# vhf-radio.net
KiCad netlist of a schematic drawn in EAGLE
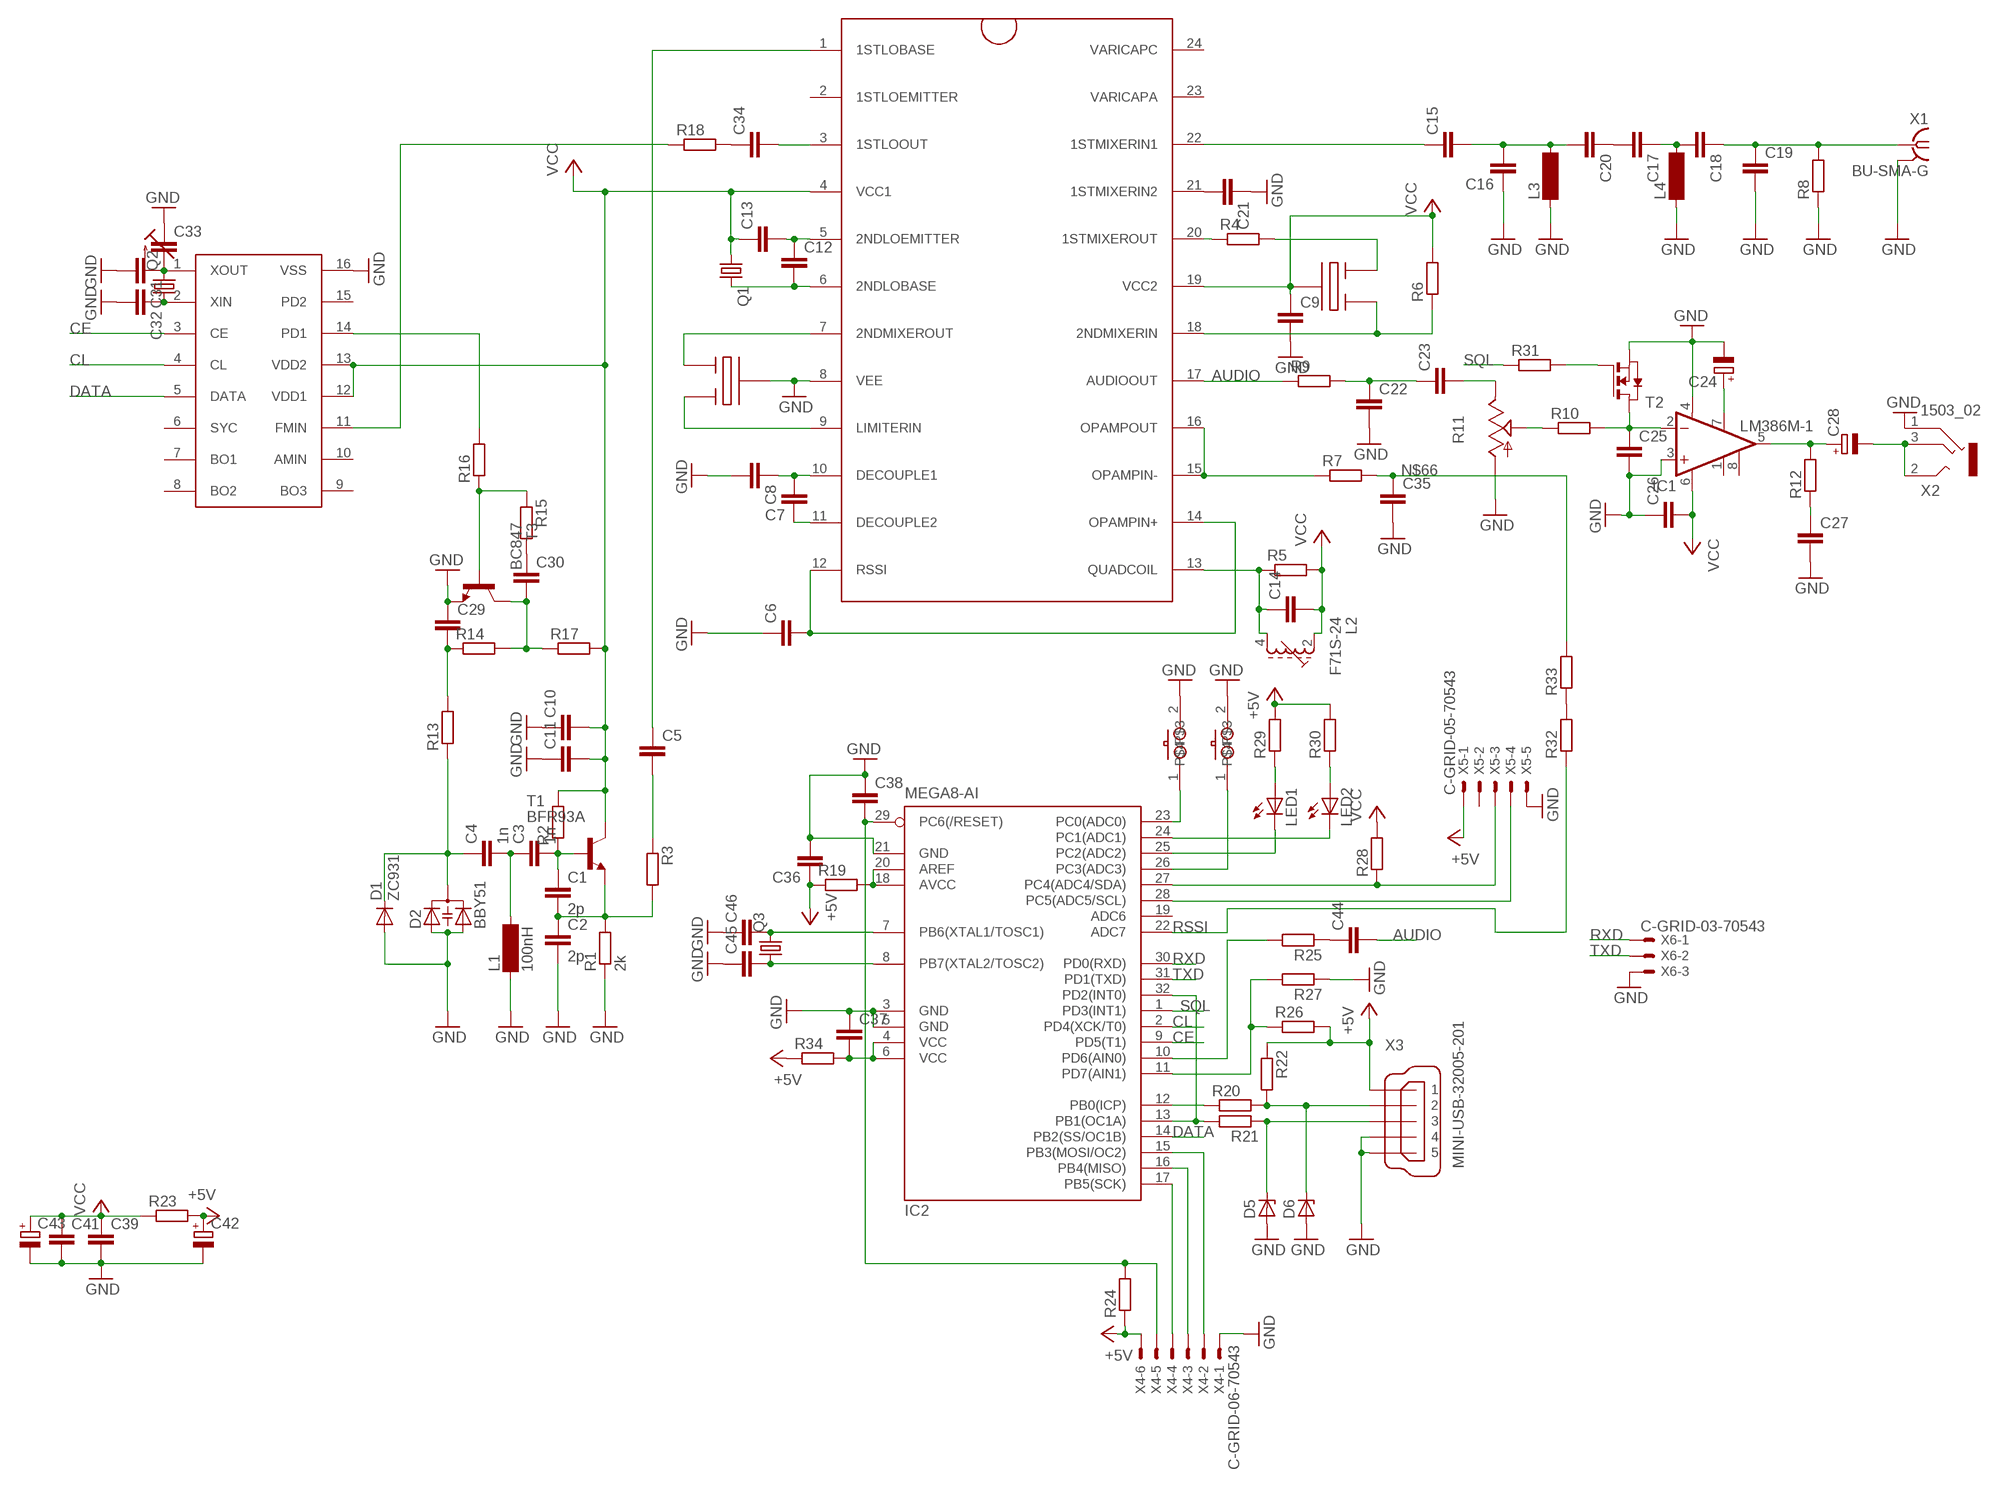
[diagram p0: schematic, sheet 1]

(export (version "E")
  (design (tool "Eeschema 10.0.6"))
  (components
    (comp (ref "C1")
      (value "2p")
      (footprint "eagle-import:C0805")
      (libsource (lib "eagle-import") (part "resistor_C-EUC0805"))
    )
    (comp (ref "C2")
      (value "2p")
      (footprint "eagle-import:C0805")
      (libsource (lib "eagle-import") (part "resistor_C-EUC0805"))
    )
    (comp (ref "C3")
      (value "1n")
      (footprint "eagle-import:C0805")
      (libsource (lib "eagle-import") (part "resistor_C-EUC0805"))
    )
    (comp (ref "C4")
      (value "1n")
      (footprint "eagle-import:C0805")
      (libsource (lib "eagle-import") (part "resistor_C-EUC0805"))
    )
    (comp (ref "C5")
      (value "C-EUC0805")
      (footprint "eagle-import:C0805")
      (libsource (lib "eagle-import") (part "C-EUC0805"))
    )
    (comp (ref "C6")
      (value "C-EUC0805")
      (footprint "eagle-import:C0805")
      (libsource (lib "eagle-import") (part "C-EUC0805"))
    )
    (comp (ref "C7")
      (value "C-EUC0805")
      (footprint "eagle-import:C0805")
      (libsource (lib "eagle-import") (part "C-EUC0805"))
    )
    (comp (ref "C8")
      (value "C-EUC0805")
      (footprint "eagle-import:C0805")
      (libsource (lib "eagle-import") (part "C-EUC0805"))
    )
    (comp (ref "C9")
      (value "C-EUC0805")
      (footprint "eagle-import:C0805")
      (libsource (lib "eagle-import") (part "C-EUC0805"))
    )
    (comp (ref "C10")
      (value "C-EUC0805")
      (footprint "eagle-import:C0805")
      (libsource (lib "eagle-import") (part "C-EUC0805"))
    )
    (comp (ref "C11")
      (value "C-EUC0805")
      (footprint "eagle-import:C0805")
      (libsource (lib "eagle-import") (part "C-EUC0805"))
    )
    (comp (ref "C12")
      (value "C-EUC0805")
      (footprint "eagle-import:C0805")
      (libsource (lib "eagle-import") (part "resistor_C-EUC0805"))
    )
    (comp (ref "C13")
      (value "C-EUC0805")
      (footprint "eagle-import:C0805")
      (libsource (lib "eagle-import") (part "resistor_C-EUC0805"))
    )
    (comp (ref "C14")
      (value "C-EUC0805")
      (footprint "eagle-import:C0805")
      (libsource (lib "eagle-import") (part "C-EUC0805"))
    )
    (comp (ref "C15")
      (value "C-EUC0805")
      (footprint "eagle-import:C0805")
      (libsource (lib "eagle-import") (part "resistor_C-EUC0805"))
    )
    (comp (ref "C16")
      (value "C-EUC0805")
      (footprint "eagle-import:C0805")
      (libsource (lib "eagle-import") (part "resistor_C-EUC0805"))
    )
    (comp (ref "C17")
      (value "C-EUC0805")
      (footprint "eagle-import:C0805")
      (libsource (lib "eagle-import") (part "resistor_C-EUC0805"))
    )
    (comp (ref "C18")
      (value "C-EUC0805")
      (footprint "eagle-import:C0805")
      (libsource (lib "eagle-import") (part "resistor_C-EUC0805"))
    )
    (comp (ref "C19")
      (value "C-EUC0805")
      (footprint "eagle-import:C0805")
      (libsource (lib "eagle-import") (part "resistor_C-EUC0805"))
    )
    (comp (ref "C20")
      (value "C-EUC0805")
      (footprint "eagle-import:C0805")
      (libsource (lib "eagle-import") (part "resistor_C-EUC0805"))
    )
    (comp (ref "C21")
      (value "C-EUC0805")
      (footprint "eagle-import:C0805")
      (libsource (lib "eagle-import") (part "resistor_C-EUC0805"))
    )
    (comp (ref "C22")
      (value "C-EUC0805")
      (footprint "eagle-import:C0805")
      (libsource (lib "eagle-import") (part "resistor_C-EUC0805"))
    )
    (comp (ref "C23")
      (value "C-EUC0805")
      (footprint "eagle-import:C0805")
      (libsource (lib "eagle-import") (part "resistor_C-EUC0805"))
    )
    (comp (ref "C24")
      (value "CPOL-EU153CLV-0505")
      (footprint "eagle-import:153CLV-0505")
      (libsource (lib "eagle-import") (part "CPOL-EU153CLV-0505"))
    )
    (comp (ref "C25")
      (value "C-EUC0805")
      (footprint "eagle-import:C0805")
      (libsource (lib "eagle-import") (part "C-EUC0805"))
    )
    (comp (ref "C26")
      (value "C-EUC0805")
      (footprint "eagle-import:C0805")
      (libsource (lib "eagle-import") (part "C-EUC0805"))
    )
    (comp (ref "C27")
      (value "C-EUC0805")
      (footprint "eagle-import:C0805")
      (libsource (lib "eagle-import") (part "C-EUC0805"))
    )
    (comp (ref "C28")
      (value "CPOL-EU153CLV-0605")
      (footprint "eagle-import:153CLV-0605")
      (libsource (lib "eagle-import") (part "resistor_CPOL-EU153CLV-0605"))
    )
    (comp (ref "C29")
      (value "C-EUC0805")
      (footprint "eagle-import:C0805")
      (libsource (lib "eagle-import") (part "C-EUC0805"))
    )
    (comp (ref "C30")
      (value "C-EUC0805")
      (footprint "eagle-import:C0805")
      (libsource (lib "eagle-import") (part "C-EUC0805"))
    )
    (comp (ref "C31")
      (value "C-EUC0805")
      (footprint "eagle-import:C0805")
      (libsource (lib "eagle-import") (part "C-EUC0805"))
    )
    (comp (ref "C32")
      (value "C-EUC0805")
      (footprint "eagle-import:C0805")
      (libsource (lib "eagle-import") (part "C-EUC0805"))
    )
    (comp (ref "C33")
      (value "C-TRIMM3018_12")
      (footprint "eagle-import:CTRIM3018_12")
      (libsource (lib "eagle-import") (part "C-TRIMM3018_12"))
    )
    (comp (ref "C34")
      (value "C-EUC0805")
      (footprint "eagle-import:C0805")
      (libsource (lib "eagle-import") (part "C-EUC0805"))
    )
    (comp (ref "C35")
      (value "C-EUC0805")
      (footprint "eagle-import:C0805")
      (libsource (lib "eagle-import") (part "C-EUC0805"))
    )
    (comp (ref "C36")
      (value "C-EUC0805")
      (footprint "eagle-import:C0805")
      (libsource (lib "eagle-import") (part "C-EUC0805"))
    )
    (comp (ref "C37")
      (value "C-EUC0805")
      (footprint "eagle-import:C0805")
      (libsource (lib "eagle-import") (part "C-EUC0805"))
    )
    (comp (ref "C38")
      (value "C-EU075-032X103")
      (footprint "eagle-import:C075-032X103")
      (libsource (lib "eagle-import") (part "C-EU075-032X103"))
    )
    (comp (ref "C39")
      (value "C-EUC0805")
      (footprint "eagle-import:C0805")
      (libsource (lib "eagle-import") (part "C-EUC0805"))
    )
    (comp (ref "C41")
      (value "C-EUC0805")
      (footprint "eagle-import:C0805")
      (libsource (lib "eagle-import") (part "C-EUC0805"))
    )
    (comp (ref "C42")
      (value "CPOL-EU175TMP-0808")
      (footprint "eagle-import:175TMP-0808")
      (libsource (lib "eagle-import") (part "CPOL-EU175TMP-0808"))
    )
    (comp (ref "C43")
      (value "CPOL-EU175TMP-0808")
      (footprint "eagle-import:175TMP-0808")
      (libsource (lib "eagle-import") (part "CPOL-EU175TMP-0808"))
    )
    (comp (ref "C44")
      (value "C-EUC0805")
      (footprint "eagle-import:C0805")
      (libsource (lib "eagle-import") (part "C-EUC0805"))
    )
    (comp (ref "C45")
      (value "C-EUC0805")
      (footprint "eagle-import:C0805")
      (libsource (lib "eagle-import") (part "C-EUC0805"))
    )
    (comp (ref "C46")
      (value "C-EUC0805")
      (footprint "eagle-import:C0805")
      (libsource (lib "eagle-import") (part "C-EUC0805"))
    )
    (comp (ref "D1")
      (value "ZC931")
      (footprint "eagle-import:MINIMELF")
      (libsource (lib "eagle-import") (part "DIODE-MINIMELF"))
    )
    (comp (ref "D2")
      (value "BBY51")
      (footprint "eagle-import:SOT23")
      (libsource (lib "eagle-import") (part "BBY51"))
    )
    (comp (ref "D5")
      (value "ZENER-DIODESOD80C")
      (footprint "eagle-import:SOD80C")
      (libsource (lib "eagle-import") (part "ZENER-DIODESOD80C"))
    )
    (comp (ref "D6")
      (value "ZENER-DIODESOD80C")
      (footprint "eagle-import:SOD80C")
      (libsource (lib "eagle-import") (part "ZENER-DIODESOD80C"))
    )
    (comp (ref "IC1")
      (value "LM386M-1")
      (footprint "eagle-import:SO08")
      (libsource (lib "eagle-import") (part "LM386?-M1"))
    )
    (comp (ref "IC2")
      (value "MEGA8-AI")
      (footprint "eagle-import:TQFP32-08")
      (libsource (lib "eagle-import") (part "MEGA8-AI"))
    )
    (comp (ref "L1")
      (value "100nH")
      (footprint "eagle-import:SM-1206")
      (libsource (lib "eagle-import") (part "SM-1206"))
    )
    (comp (ref "L2")
      (value "F71S-24")
      (footprint "eagle-import:71S")
      (libsource (lib "eagle-import") (part "F71S-24"))
    )
    (comp (ref "L3")
      (value "SM-1206")
      (footprint "eagle-import:SM-1206")
      (libsource (lib "eagle-import") (part "SM-1206"))
    )
    (comp (ref "L4")
      (value "SM-1206")
      (footprint "eagle-import:SM-1206")
      (libsource (lib "eagle-import") (part "SM-1206"))
    )
    (comp (ref "LED1")
      (value "LEDCHIPLED_0805")
      (footprint "eagle-import:CHIPLED_0805")
      (libsource (lib "eagle-import") (part "LEDCHIPLED_0805"))
    )
    (comp (ref "LED2")
      (value "LEDCHIPLED_0805")
      (footprint "eagle-import:CHIPLED_0805")
      (libsource (lib "eagle-import") (part "LEDCHIPLED_0805"))
    )
    (comp (ref "Q1")
      (value "CRYSTALHC49UP")
      (footprint "eagle-import:HC49UP")
      (libsource (lib "eagle-import") (part "CRYSTALHC49UP"))
    )
    (comp (ref "Q2")
      (value "CRYSTALHC49UP")
      (footprint "eagle-import:HC49UP")
      (libsource (lib "eagle-import") (part "CRYSTALHC49UP"))
    )
    (comp (ref "Q3")
      (value "CRYSTALHC49UP")
      (footprint "eagle-import:HC49UP")
      (libsource (lib "eagle-import") (part "CRYSTALHC49UP"))
    )
    (comp (ref "R1")
      (value "2k")
      (footprint "eagle-import:R0805")
      (libsource (lib "eagle-import") (part "resistor_R-EU_R0805"))
    )
    (comp (ref "R2")
      (value "R-EU_R0805")
      (footprint "eagle-import:R0805")
      (libsource (lib "eagle-import") (part "resistor_R-EU_R0805"))
    )
    (comp (ref "R3")
      (value "R-EU_R0805")
      (footprint "eagle-import:R0805")
      (libsource (lib "eagle-import") (part "R-EU_R0805"))
    )
    (comp (ref "R4")
      (value "R-EU_R0805")
      (footprint "eagle-import:R0805")
      (libsource (lib "eagle-import") (part "R-EU_R0805"))
    )
    (comp (ref "R5")
      (value "R-EU_R0805")
      (footprint "eagle-import:R0805")
      (libsource (lib "eagle-import") (part "R-EU_R0805"))
    )
    (comp (ref "R6")
      (value "R-EU_R0805")
      (footprint "eagle-import:R0805")
      (libsource (lib "eagle-import") (part "R-EU_R0805"))
    )
    (comp (ref "R7")
      (value "R-EU_R0805")
      (footprint "eagle-import:R0805")
      (libsource (lib "eagle-import") (part "R-EU_R0805"))
    )
    (comp (ref "R8")
      (value "R-EU_R0805")
      (footprint "eagle-import:R0805")
      (libsource (lib "eagle-import") (part "resistor_R-EU_R0805"))
    )
    (comp (ref "R9")
      (value "R-EU_R0805")
      (footprint "eagle-import:R0805")
      (libsource (lib "eagle-import") (part "R-EU_R0805"))
    )
    (comp (ref "R10")
      (value "R-EU_R0805")
      (footprint "eagle-import:R0805")
      (libsource (lib "eagle-import") (part "R-EU_R0805"))
    )
    (comp (ref "R11")
      (value "TRIM_US-CIP20C-6MM")
      (footprint "eagle-import:CIP20C-6MM")
      (libsource (lib "eagle-import") (part "TRIM_US-CIP20C-6MM"))
    )
    (comp (ref "R12")
      (value "R-EU_R0805")
      (footprint "eagle-import:R0805")
      (libsource (lib "eagle-import") (part "R-EU_R0805"))
    )
    (comp (ref "R13")
      (value "R-EU_R0805")
      (footprint "eagle-import:R0805")
      (libsource (lib "eagle-import") (part "R-EU_R0805"))
    )
    (comp (ref "R14")
      (value "R-EU_R0805")
      (footprint "eagle-import:R0805")
      (libsource (lib "eagle-import") (part "R-EU_R0805"))
    )
    (comp (ref "R15")
      (value "R-EU_R0805")
      (footprint "eagle-import:R0805")
      (libsource (lib "eagle-import") (part "R-EU_R0805"))
    )
    (comp (ref "R16")
      (value "R-EU_R0805")
      (footprint "eagle-import:R0805")
      (libsource (lib "eagle-import") (part "R-EU_R0805"))
    )
    (comp (ref "R17")
      (value "R-EU_R0805")
      (footprint "eagle-import:R0805")
      (libsource (lib "eagle-import") (part "R-EU_R0805"))
    )
    (comp (ref "R18")
      (value "R-EU_R0805")
      (footprint "eagle-import:R0805")
      (libsource (lib "eagle-import") (part "R-EU_R0805"))
    )
    (comp (ref "R19")
      (value "R-EU_R0805")
      (footprint "eagle-import:R0805")
      (libsource (lib "eagle-import") (part "R-EU_R0805"))
    )
    (comp (ref "R20")
      (value "R-EU_R0805")
      (footprint "eagle-import:R0805")
      (libsource (lib "eagle-import") (part "R-EU_R0805"))
    )
    (comp (ref "R21")
      (value "R-EU_R0805")
      (footprint "eagle-import:R0805")
      (libsource (lib "eagle-import") (part "R-EU_R0805"))
    )
    (comp (ref "R22")
      (value "R-EU_R0805")
      (footprint "eagle-import:R0805")
      (libsource (lib "eagle-import") (part "R-EU_R0805"))
    )
    (comp (ref "R23")
      (value "R-EU_0207/10")
      (footprint "eagle-import:0207_10")
      (libsource (lib "eagle-import") (part "resistor_R-EU_0207/10"))
    )
    (comp (ref "R24")
      (value "R-EU_R0805")
      (footprint "eagle-import:R0805")
      (libsource (lib "eagle-import") (part "R-EU_R0805"))
    )
    (comp (ref "R25")
      (value "R-EU_R0805")
      (footprint "eagle-import:R0805")
      (libsource (lib "eagle-import") (part "R-EU_R0805"))
    )
    (comp (ref "R26")
      (value "R-EU_R0805")
      (footprint "eagle-import:R0805")
      (libsource (lib "eagle-import") (part "R-EU_R0805"))
    )
    (comp (ref "R27")
      (value "R-EU_R0805")
      (footprint "eagle-import:R0805")
      (libsource (lib "eagle-import") (part "R-EU_R0805"))
    )
    (comp (ref "R28")
      (value "R-EU_0207/10")
      (footprint "eagle-import:0207_10")
      (libsource (lib "eagle-import") (part "resistor_R-EU_0207/10"))
    )
    (comp (ref "R29")
      (value "R-EU_R0805")
      (footprint "eagle-import:R0805")
      (libsource (lib "eagle-import") (part "R-EU_R0805"))
    )
    (comp (ref "R30")
      (value "R-EU_R0805")
      (footprint "eagle-import:R0805")
      (libsource (lib "eagle-import") (part "R-EU_R0805"))
    )
    (comp (ref "R31")
      (value "R-EU_R1206")
      (footprint "eagle-import:R1206")
      (libsource (lib "eagle-import") (part "R-EU_R1206"))
    )
    (comp (ref "R32")
      (value "R-EU_0207/10")
      (footprint "eagle-import:0207_10")
      (libsource (lib "eagle-import") (part "resistor_R-EU_0207/10"))
    )
    (comp (ref "R33")
      (value "R-EU_0207/10")
      (footprint "eagle-import:0207_10")
      (libsource (lib "eagle-import") (part "resistor_R-EU_0207/10"))
    )
    (comp (ref "R34")
      (value "R-EU_0207/10")
      (footprint "eagle-import:0207_10")
      (libsource (lib "eagle-import") (part "resistor_R-EU_0207/10"))
    )
    (comp (ref "T1")
      (value "BFR93A")
      (footprint "eagle-import:SOT23-BEC")
      (libsource (lib "eagle-import") (part "-NPN-SOT23-BECBFR53"))
    )
    (comp (ref "T2")
      (value "NMOSSOT23")
      (footprint "eagle-import:SOT-23")
      (libsource (lib "eagle-import") (part "NMOSSOT23"))
    )
    (comp (ref "T3")
      (value "BC847")
      (footprint "eagle-import:SOT23")
      (libsource (lib "eagle-import") (part "BC847"))
    )
    (comp (ref "U$1")
      (value "MC13135P-SMD")
      (footprint "eagle-import:DIP-SMD")
      (libsource (lib "eagle-import") (part "MC13135P-SMD"))
    )
    (comp (ref "U$2")
      (value "QFILTER")
      (footprint "eagle-import:SIP3-SMD")
      (libsource (lib "eagle-import") (part "QFILTER"))
    )
    (comp (ref "U$3")
      (value "QFILTER")
      (footprint "eagle-import:SIP3-SMD")
      (libsource (lib "eagle-import") (part "QFILTER"))
    )
    (comp (ref "U$4")
      (value "LM7001-DIPSMD")
      (footprint "eagle-import:DIP16-SMD")
      (libsource (lib "eagle-import") (part "LM7001-DIPSMD"))
    )
    (comp (ref "U$5")
      (value "TS-1")
      (footprint "eagle-import:TS-1")
      (libsource (lib "eagle-import") (part "TS-1"))
    )
    (comp (ref "U$6")
      (value "TS-1")
      (footprint "eagle-import:TS-1")
      (libsource (lib "eagle-import") (part "TS-1"))
    )
    (comp (ref "X1")
      (value "BU-SMA-G")
      (footprint "eagle-import:BU-SMA-G")
      (libsource (lib "eagle-import") (part "BU-SMA-G"))
    )
    (comp (ref "X2")
      (value "1503_02")
      (footprint "eagle-import:1503_02")
      (libsource (lib "eagle-import") (part "1503_02"))
    )
    (comp (ref "X3")
      (value "MINI-USB-32005-201")
      (footprint "eagle-import:32005-201")
      (libsource (lib "eagle-import") (part "MINI-USB-32005-201"))
    )
    (comp (ref "X4")
      (value "C-GRID-06-70543")
      (footprint "eagle-import:70543-06")
      (libsource (lib "eagle-import") (part "C-GRID-06-70543"))
    )
    (comp (ref "X5")
      (value "C-GRID-05-70543")
      (footprint "eagle-import:70543-05")
      (libsource (lib "eagle-import") (part "C-GRID-05-70543"))
    )
    (comp (ref "X6")
      (value "C-GRID-03-70543")
      (footprint "eagle-import:70543-03")
      (libsource (lib "eagle-import") (part "C-GRID-03-70543"))
    )
  )
  (nets
    (net (code "1") (name "+5V") (class "Default")
      (node (ref "C36") (pin "1") (pinfunction "1_1") (pintype "passive"))
      (node (ref "C42") (pin "+") (pinfunction "+_+") (pintype "passive"))
      (node (ref "R19") (pin "1") (pinfunction "1_1") (pintype "passive"))
      (node (ref "R22") (pin "1") (pinfunction "1_1") (pintype "passive"))
      (node (ref "R23") (pin "2") (pinfunction "2_2") (pintype "passive"))
      (node (ref "R24") (pin "1") (pinfunction "1_1") (pintype "passive"))
      (node (ref "R26") (pin "2") (pinfunction "2_2") (pintype "passive"))
      (node (ref "R29") (pin "2") (pinfunction "2_2") (pintype "passive"))
      (node (ref "R30") (pin "2") (pinfunction "2_2") (pintype "passive"))
      (node (ref "R34") (pin "1") (pinfunction "1_1") (pintype "passive"))
      (node (ref "X3") (pin "1") (pinfunction "1_1") (pintype "passive"))
      (node (ref "X4") (pin "6") (pinfunction "S_6") (pintype "passive"))
      (node (ref "X5") (pin "1") (pinfunction "S_1") (pintype "passive"))
    )
    (net (code "2") (name "/AUDIO") (class "Default")
      (node (ref "C44") (pin "2") (pinfunction "2_2") (pintype "passive"))
      (node (ref "R9") (pin "1") (pinfunction "1_1") (pintype "passive"))
      (node (ref "U$1") (pin "17") (pinfunction "AUDIOOUT_17") (pintype "bidirectional"))
    )
    (net (code "3") (name "/CE") (class "Default")
      (node (ref "IC2") (pin "9") (pinfunction "PD5(T1)_9") (pintype "bidirectional"))
      (node (ref "U$4") (pin "3") (pinfunction "CE_3") (pintype "bidirectional"))
    )
    (net (code "4") (name "/CL") (class "Default")
      (node (ref "IC2") (pin "2") (pinfunction "PD4(XCK/T0)_2") (pintype "bidirectional"))
      (node (ref "U$4") (pin "4") (pinfunction "CL_4") (pintype "bidirectional"))
    )
    (net (code "5") (name "/DATA") (class "Default")
      (node (ref "IC2") (pin "14") (pinfunction "PB2(SS/OC1B)_14") (pintype "bidirectional"))
      (node (ref "U$4") (pin "5") (pinfunction "DATA_5") (pintype "bidirectional"))
    )
    (net (code "6") (name "/N$66") (class "Default")
      (node (ref "C35") (pin "1") (pinfunction "1_1") (pintype "passive"))
      (node (ref "R33") (pin "2") (pinfunction "2_2") (pintype "passive"))
      (node (ref "R7") (pin "2") (pinfunction "2_2") (pintype "passive"))
    )
    (net (code "7") (name "/RSSI") (class "Default")
      (node (ref "IC2") (pin "22") (pinfunction "ADC7_22") (pintype "bidirectional"))
      (node (ref "R32") (pin "1") (pinfunction "1_1") (pintype "passive"))
    )
    (net (code "8") (name "/RXD") (class "Default")
      (node (ref "IC2") (pin "30") (pinfunction "PD0(RXD)_30") (pintype "bidirectional"))
      (node (ref "X6") (pin "1") (pinfunction "S_1") (pintype "passive"))
    )
    (net (code "9") (name "/SQL") (class "Default")
      (node (ref "IC2") (pin "1") (pinfunction "PD3(INT1)_1") (pintype "bidirectional"))
      (node (ref "R31") (pin "1") (pinfunction "1_1") (pintype "passive"))
    )
    (net (code "10") (name "/TXD") (class "Default")
      (node (ref "IC2") (pin "31") (pinfunction "PD1(TXD)_31") (pintype "bidirectional"))
      (node (ref "X6") (pin "2") (pinfunction "S_2") (pintype "passive"))
    )
    (net (code "11") (name "GND") (class "Default")
      (node (ref "C10") (pin "1") (pinfunction "1_1") (pintype "passive"))
      (node (ref "C11") (pin "1") (pinfunction "1_1") (pintype "passive"))
      (node (ref "C16") (pin "1") (pinfunction "1_1") (pintype "passive"))
      (node (ref "C19") (pin "2") (pinfunction "2_2") (pintype "passive"))
      (node (ref "C2") (pin "2") (pinfunction "2_2") (pintype "passive"))
      (node (ref "C21") (pin "1") (pinfunction "1_1") (pintype "passive"))
      (node (ref "C22") (pin "2") (pinfunction "2_2") (pintype "passive"))
      (node (ref "C24") (pin "-") (pinfunction "-_-") (pintype "passive"))
      (node (ref "C25") (pin "2") (pinfunction "2_2") (pintype "passive"))
      (node (ref "C26") (pin "1") (pinfunction "1_1") (pintype "passive"))
      (node (ref "C27") (pin "2") (pinfunction "2_2") (pintype "passive"))
      (node (ref "C29") (pin "1") (pinfunction "1_1") (pintype "passive"))
      (node (ref "C31") (pin "2") (pinfunction "2_2") (pintype "passive"))
      (node (ref "C32") (pin "2") (pinfunction "2_2") (pintype "passive"))
      (node (ref "C33") (pin "+") (pinfunction "E_+") (pintype "passive"))
      (node (ref "C35") (pin "2") (pinfunction "2_2") (pintype "passive"))
      (node (ref "C36") (pin "2") (pinfunction "2_2") (pintype "passive"))
      (node (ref "C37") (pin "1") (pinfunction "1_1") (pintype "passive"))
      (node (ref "C38") (pin "1") (pinfunction "1_1") (pintype "passive"))
      (node (ref "C39") (pin "2") (pinfunction "2_2") (pintype "passive"))
      (node (ref "C41") (pin "2") (pinfunction "2_2") (pintype "passive"))
      (node (ref "C42") (pin "-") (pinfunction "-_-") (pintype "passive"))
      (node (ref "C43") (pin "-") (pinfunction "-_-") (pintype "passive"))
      (node (ref "C45") (pin "1") (pinfunction "1_1") (pintype "passive"))
      (node (ref "C46") (pin "1") (pinfunction "1_1") (pintype "passive"))
      (node (ref "C6") (pin "1") (pinfunction "1_1") (pintype "passive"))
      (node (ref "C8") (pin "2") (pinfunction "2_2") (pintype "passive"))
      (node (ref "C9") (pin "2") (pinfunction "2_2") (pintype "passive"))
      (node (ref "D1") (pin "A") (pinfunction "A_A") (pintype "passive"))
      (node (ref "D2") (pin "1") (pinfunction "A1_1") (pintype "passive"))
      (node (ref "D2") (pin "2") (pinfunction "A2_2") (pintype "passive"))
      (node (ref "D5") (pin "A") (pinfunction "A_A") (pintype "passive"))
      (node (ref "D6") (pin "A") (pinfunction "A_A") (pintype "passive"))
      (node (ref "IC1") (pin "3") (pinfunction "+IN_3") (pintype "input"))
      (node (ref "IC1") (pin "4") (pinfunction "GND_4") (pintype "power_in"))
      (node (ref "IC2") (pin "21") (pinfunction "GND_21") (pintype "power_in"))
      (node (ref "IC2") (pin "3") (pinfunction "GND_3") (pintype "power_in"))
      (node (ref "IC2") (pin "5") (pinfunction "GND_5") (pintype "power_in"))
      (node (ref "L1") (pin "1") (pinfunction "1_1") (pintype "passive"))
      (node (ref "L3") (pin "1") (pinfunction "1_1") (pintype "passive"))
      (node (ref "L4") (pin "1") (pinfunction "1_1") (pintype "passive"))
      (node (ref "R1") (pin "1") (pinfunction "1_1") (pintype "passive"))
      (node (ref "R11") (pin "A") (pinfunction "A_A") (pintype "passive"))
      (node (ref "R27") (pin "1") (pinfunction "1_1") (pintype "passive"))
      (node (ref "R8") (pin "1") (pinfunction "1_1") (pintype "passive"))
      (node (ref "T2") (pin "2") (pinfunction "S_2") (pintype "passive"))
      (node (ref "T3") (pin "2") (pinfunction "E_2") (pintype "passive"))
      (node (ref "U$1") (pin "8") (pinfunction "VEE_8") (pintype "bidirectional"))
      (node (ref "U$2") (pin "P$2") (pinfunction "2_P$2") (pintype "bidirectional"))
      (node (ref "U$4") (pin "16") (pinfunction "VSS_16") (pintype "bidirectional"))
      (node (ref "U$5") (pin "2") (pinfunction "P$4_2") (pintype "bidirectional"))
      (node (ref "U$6") (pin "2") (pinfunction "P$4_2") (pintype "bidirectional"))
      (node (ref "X1") (pin "2") (pinfunction "GND_2") (pintype "power_in"))
      (node (ref "X2") (pin "1") (pinfunction "1_1") (pintype "passive"))
      (node (ref "X3") (pin "4") (pinfunction "4_4") (pintype "passive"))
      (node (ref "X3") (pin "5") (pinfunction "5_5") (pintype "passive"))
      (node (ref "X4") (pin "1") (pinfunction "S_1") (pintype "passive"))
      (node (ref "X5") (pin "5") (pinfunction "S_5") (pintype "passive"))
      (node (ref "X6") (pin "3") (pinfunction "S_3") (pintype "passive"))
    )
    (net (code "12") (name "Net-(C1-Pad1)") (class "Default")
      (node (ref "C1") (pin "1") (pinfunction "1_1") (pintype "passive"))
      (node (ref "C3") (pin "2") (pinfunction "2_2") (pintype "passive"))
      (node (ref "R2") (pin "1") (pinfunction "1_1") (pintype "passive"))
      (node (ref "T1") (pin "B") (pinfunction "B_B") (pintype "passive"))
    )
    (net (code "13") (name "Net-(C1-Pad2)") (class "Default")
      (node (ref "C1") (pin "2") (pinfunction "2_2") (pintype "passive"))
      (node (ref "C2") (pin "1") (pinfunction "1_1") (pintype "passive"))
      (node (ref "R1") (pin "2") (pinfunction "2_2") (pintype "passive"))
      (node (ref "R3") (pin "2") (pinfunction "2_2") (pintype "passive"))
      (node (ref "T1") (pin "E") (pinfunction "E_E") (pintype "passive"))
    )
    (net (code "14") (name "Net-(C3-Pad1)") (class "Default")
      (node (ref "C3") (pin "1") (pinfunction "1_1") (pintype "passive"))
      (node (ref "C4") (pin "2") (pinfunction "2_2") (pintype "passive"))
      (node (ref "L1") (pin "2") (pinfunction "2_2") (pintype "passive"))
    )
    (net (code "15") (name "Net-(C5-Pad2)") (class "Default")
      (node (ref "C5") (pin "2") (pinfunction "2_2") (pintype "passive"))
      (node (ref "R3") (pin "1") (pinfunction "1_1") (pintype "passive"))
    )
    (net (code "16") (name "Net-(C15-Pad2)") (class "Default")
      (node (ref "C15") (pin "2") (pinfunction "2_2") (pintype "passive"))
      (node (ref "C16") (pin "2") (pinfunction "2_2") (pintype "passive"))
      (node (ref "C20") (pin "2") (pinfunction "2_2") (pintype "passive"))
      (node (ref "L3") (pin "2") (pinfunction "2_2") (pintype "passive"))
    )
    (net (code "17") (name "Net-(C17-Pad1)") (class "Default")
      (node (ref "C17") (pin "1") (pinfunction "1_1") (pintype "passive"))
      (node (ref "C18") (pin "2") (pinfunction "2_2") (pintype "passive"))
      (node (ref "L4") (pin "2") (pinfunction "2_2") (pintype "passive"))
    )
    (net (code "18") (name "Net-(C17-Pad2)") (class "Default")
      (node (ref "C17") (pin "2") (pinfunction "2_2") (pintype "passive"))
      (node (ref "C20") (pin "1") (pinfunction "1_1") (pintype "passive"))
    )
    (net (code "19") (name "Net-(C18-Pad1)") (class "Default")
      (node (ref "C18") (pin "1") (pinfunction "1_1") (pintype "passive"))
      (node (ref "C19") (pin "1") (pinfunction "1_1") (pintype "passive"))
      (node (ref "R8") (pin "2") (pinfunction "2_2") (pintype "passive"))
      (node (ref "X1") (pin "1") (pinfunction "1_1") (pintype "passive"))
    )
    (net (code "20") (name "Net-(C22-Pad1)") (class "Default")
      (node (ref "C22") (pin "1") (pinfunction "1_1") (pintype "passive"))
      (node (ref "C23") (pin "1") (pinfunction "1_1") (pintype "passive"))
      (node (ref "R9") (pin "2") (pinfunction "2_2") (pintype "passive"))
    )
    (net (code "21") (name "Net-(C23-Pad2)") (class "Default")
      (node (ref "C23") (pin "2") (pinfunction "2_2") (pintype "passive"))
      (node (ref "R11") (pin "E") (pinfunction "E_E") (pintype "passive"))
    )
    (net (code "22") (name "Net-(C27-Pad1)") (class "Default")
      (node (ref "C27") (pin "1") (pinfunction "1_1") (pintype "passive"))
      (node (ref "R12") (pin "1") (pinfunction "1_1") (pintype "passive"))
    )
    (net (code "23") (name "Net-(C28-Pad-)") (class "Default")
      (node (ref "C28") (pin "-") (pinfunction "-_-") (pintype "passive"))
      (node (ref "X2") (pin "2") (pinfunction "2_2") (pintype "passive"))
      (node (ref "X2") (pin "3") (pinfunction "3_3") (pintype "passive"))
    )
    (net (code "24") (name "Net-(C29-Pad2)") (class "Default")
      (node (ref "C29") (pin "2") (pinfunction "2_2") (pintype "passive"))
      (node (ref "R13") (pin "2") (pinfunction "2_2") (pintype "passive"))
      (node (ref "R14") (pin "1") (pinfunction "1_1") (pintype "passive"))
    )
    (net (code "25") (name "Net-(C30-Pad1)") (class "Default")
      (node (ref "C30") (pin "1") (pinfunction "1_1") (pintype "passive"))
      (node (ref "R15") (pin "2") (pinfunction "2_2") (pintype "passive"))
    )
    (net (code "26") (name "Net-(C33-A)") (class "Default")
      (node (ref "C31") (pin "1") (pinfunction "1_1") (pintype "passive"))
      (node (ref "C33") (pin "-") (pinfunction "A_-") (pintype "passive"))
      (node (ref "Q2") (pin "2") (pinfunction "2_2") (pintype "passive"))
      (node (ref "U$4") (pin "1") (pinfunction "XOUT_1") (pintype "bidirectional"))
    )
    (net (code "27") (name "Net-(C34-Pad1)") (class "Default")
      (node (ref "C34") (pin "1") (pinfunction "1_1") (pintype "passive"))
      (node (ref "R18") (pin "2") (pinfunction "2_2") (pintype "passive"))
    )
    (net (code "28") (name "Net-(C37-Pad2)") (class "Default")
      (node (ref "C37") (pin "2") (pinfunction "2_2") (pintype "passive"))
      (node (ref "IC2") (pin "4") (pinfunction "VCC_4") (pintype "power_in"))
      (node (ref "IC2") (pin "6") (pinfunction "VCC_6") (pintype "power_in"))
      (node (ref "R34") (pin "2") (pinfunction "2_2") (pintype "passive"))
    )
    (net (code "29") (name "Net-(C44-Pad1)") (class "Default")
      (node (ref "C44") (pin "1") (pinfunction "1_1") (pintype "passive"))
      (node (ref "R25") (pin "1") (pinfunction "1_1") (pintype "passive"))
    )
    (net (code "30") (name "Net-(D2-C)") (class "Default")
      (node (ref "C4") (pin "1") (pinfunction "1_1") (pintype "passive"))
      (node (ref "D1") (pin "C") (pinfunction "C_C") (pintype "passive"))
      (node (ref "D2") (pin "3") (pinfunction "C_3") (pintype "passive"))
      (node (ref "R13") (pin "1") (pinfunction "1_1") (pintype "passive"))
    )
    (net (code "31") (name "Net-(D5-PadC)") (class "Default")
      (node (ref "D5") (pin "C") (pinfunction "C_C") (pintype "passive"))
      (node (ref "R21") (pin "1") (pinfunction "1_1") (pintype "passive"))
      (node (ref "X3") (pin "3") (pinfunction "3_3") (pintype "passive"))
    )
    (net (code "32") (name "Net-(D6-PadC)") (class "Default")
      (node (ref "D6") (pin "C") (pinfunction "C_C") (pintype "passive"))
      (node (ref "R20") (pin "2") (pinfunction "2_2") (pintype "passive"))
      (node (ref "R22") (pin "2") (pinfunction "2_2") (pintype "passive"))
      (node (ref "X3") (pin "2") (pinfunction "2_2") (pintype "passive"))
    )
    (net (code "33") (name "Net-(IC1--IN)") (class "Default")
      (node (ref "C25") (pin "1") (pinfunction "1_1") (pintype "passive"))
      (node (ref "IC1") (pin "2") (pinfunction "-IN_2") (pintype "input"))
      (node (ref "R10") (pin "2") (pinfunction "2_2") (pintype "passive"))
      (node (ref "T2") (pin "1") (pinfunction "D_1") (pintype "passive"))
    )
    (net (code "34") (name "Net-(IC1-BYPASS)") (class "Default")
      (node (ref "C24") (pin "+") (pinfunction "+_+") (pintype "passive"))
      (node (ref "IC1") (pin "7") (pinfunction "BYPASS_7") (pintype "passive"))
    )
    (net (code "35") (name "Net-(IC1-OUT)") (class "Default")
      (node (ref "C28") (pin "+") (pinfunction "+_+") (pintype "passive"))
      (node (ref "IC1") (pin "5") (pinfunction "OUT_5") (pintype "output"))
      (node (ref "R12") (pin "2") (pinfunction "2_2") (pintype "passive"))
    )
    (net (code "36") (name "Net-(IC2-AREF)") (class "Default")
      (node (ref "IC2") (pin "18") (pinfunction "AVCC_18") (pintype "power_in"))
      (node (ref "IC2") (pin "20") (pinfunction "AREF_20") (pintype "passive"))
      (node (ref "R19") (pin "2") (pinfunction "2_2") (pintype "passive"))
    )
    (net (code "37") (name "Net-(IC2-PB0(ICP))") (class "Default")
      (node (ref "IC2") (pin "12") (pinfunction "PB0(ICP)_12") (pintype "bidirectional"))
      (node (ref "R20") (pin "1") (pinfunction "1_1") (pintype "passive"))
    )
    (net (code "38") (name "Net-(IC2-PB1(OC1A))") (class "Default")
      (node (ref "IC2") (pin "13") (pinfunction "PB1(OC1A)_13") (pintype "bidirectional"))
      (node (ref "IC2") (pin "32") (pinfunction "PD2(INT0)_32") (pintype "bidirectional"))
      (node (ref "R21") (pin "2") (pinfunction "2_2") (pintype "passive"))
    )
    (net (code "39") (name "Net-(IC2-PB3(MOSI{slash}OC2))") (class "Default")
      (node (ref "IC2") (pin "15") (pinfunction "PB3(MOSI/OC2)_15") (pintype "bidirectional"))
      (node (ref "X4") (pin "2") (pinfunction "S_2") (pintype "passive"))
    )
    (net (code "40") (name "Net-(IC2-PB4(MISO))") (class "Default")
      (node (ref "IC2") (pin "16") (pinfunction "PB4(MISO)_16") (pintype "bidirectional"))
      (node (ref "X4") (pin "3") (pinfunction "S_3") (pintype "passive"))
    )
    (net (code "41") (name "Net-(IC2-PB5(SCK))") (class "Default")
      (node (ref "IC2") (pin "17") (pinfunction "PB5(SCK)_17") (pintype "bidirectional"))
      (node (ref "X4") (pin "4") (pinfunction "S_4") (pintype "passive"))
    )
    (net (code "42") (name "Net-(IC2-PB6(XTAL1{slash}TOSC1))") (class "Default")
      (node (ref "C46") (pin "2") (pinfunction "2_2") (pintype "passive"))
      (node (ref "IC2") (pin "7") (pinfunction "PB6(XTAL1/TOSC1)_7") (pintype "bidirectional"))
      (node (ref "Q3") (pin "2") (pinfunction "2_2") (pintype "passive"))
    )
    (net (code "43") (name "Net-(IC2-PB7(XTAL2{slash}TOSC2))") (class "Default")
      (node (ref "C45") (pin "2") (pinfunction "2_2") (pintype "passive"))
      (node (ref "IC2") (pin "8") (pinfunction "PB7(XTAL2/TOSC2)_8") (pintype "bidirectional"))
      (node (ref "Q3") (pin "1") (pinfunction "1_1") (pintype "passive"))
    )
    (net (code "44") (name "Net-(IC2-PC0(ADC0))") (class "Default")
      (node (ref "IC2") (pin "23") (pinfunction "PC0(ADC0)_23") (pintype "bidirectional"))
      (node (ref "U$5") (pin "1") (pinfunction "P$3_1") (pintype "bidirectional"))
    )
    (net (code "45") (name "Net-(IC2-PC1(ADC1))") (class "Default")
      (node (ref "IC2") (pin "24") (pinfunction "PC1(ADC1)_24") (pintype "bidirectional"))
      (node (ref "LED2") (pin "C") (pinfunction "C_C") (pintype "passive"))
    )
    (net (code "46") (name "Net-(IC2-PC2(ADC2))") (class "Default")
      (node (ref "IC2") (pin "25") (pinfunction "PC2(ADC2)_25") (pintype "bidirectional"))
      (node (ref "LED1") (pin "C") (pinfunction "C_C") (pintype "passive"))
    )
    (net (code "47") (name "Net-(IC2-PC3(ADC3))") (class "Default")
      (node (ref "IC2") (pin "26") (pinfunction "PC3(ADC3)_26") (pintype "bidirectional"))
      (node (ref "U$6") (pin "1") (pinfunction "P$3_1") (pintype "bidirectional"))
    )
    (net (code "48") (name "Net-(IC2-PC4(ADC4{slash}SDA))") (class "Default")
      (node (ref "IC2") (pin "27") (pinfunction "PC4(ADC4/SDA)_27") (pintype "bidirectional"))
      (node (ref "R28") (pin "1") (pinfunction "1_1") (pintype "passive"))
      (node (ref "X5") (pin "3") (pinfunction "S_3") (pintype "passive"))
    )
    (net (code "49") (name "Net-(IC2-PC5(ADC5{slash}SCL))") (class "Default")
      (node (ref "IC2") (pin "28") (pinfunction "PC5(ADC5/SCL)_28") (pintype "bidirectional"))
      (node (ref "X5") (pin "4") (pinfunction "S_4") (pintype "passive"))
    )
    (net (code "50") (name "Net-(IC2-PC6({slash}RESET))") (class "Default")
      (node (ref "C38") (pin "2") (pinfunction "2_2") (pintype "passive"))
      (node (ref "IC2") (pin "29") (pinfunction "PC6(/RESET)_29") (pintype "bidirectional"))
      (node (ref "R24") (pin "2") (pinfunction "2_2") (pintype "passive"))
      (node (ref "X4") (pin "5") (pinfunction "S_5") (pintype "passive"))
    )
    (net (code "51") (name "Net-(IC2-PD6(AIN0))") (class "Default")
      (node (ref "IC2") (pin "10") (pinfunction "PD6(AIN0)_10") (pintype "bidirectional"))
      (node (ref "R25") (pin "2") (pinfunction "2_2") (pintype "passive"))
    )
    (net (code "52") (name "Net-(IC2-PD7(AIN1))") (class "Default")
      (node (ref "IC2") (pin "11") (pinfunction "PD7(AIN1)_11") (pintype "bidirectional"))
      (node (ref "R26") (pin "1") (pinfunction "1_1") (pintype "passive"))
      (node (ref "R27") (pin "2") (pinfunction "2_2") (pintype "passive"))
    )
    (net (code "53") (name "Net-(L2A-E)") (class "Default")
      (node (ref "C14") (pin "1") (pinfunction "1_1") (pintype "passive"))
      (node (ref "L2") (pin "4") (pinfunction "E_4") (pintype "passive"))
      (node (ref "R5") (pin "1") (pinfunction "1_1") (pintype "passive"))
      (node (ref "U$1") (pin "13") (pinfunction "QUADCOIL_13") (pintype "bidirectional"))
    )
    (net (code "54") (name "Net-(LED1-PadA)") (class "Default")
      (node (ref "LED1") (pin "A") (pinfunction "A_A") (pintype "passive"))
      (node (ref "R29") (pin "1") (pinfunction "1_1") (pintype "passive"))
    )
    (net (code "55") (name "Net-(LED2-PadA)") (class "Default")
      (node (ref "LED2") (pin "A") (pinfunction "A_A") (pintype "passive"))
      (node (ref "R30") (pin "1") (pinfunction "1_1") (pintype "passive"))
    )
    (net (code "56") (name "Net-(R10-Pad1)") (class "Default")
      (node (ref "R10") (pin "1") (pinfunction "1_1") (pintype "passive"))
      (node (ref "R11") (pin "S") (pinfunction "S_S") (pintype "passive"))
    )
    (net (code "57") (name "Net-(R32-Pad2)") (class "Default")
      (node (ref "R32") (pin "2") (pinfunction "2_2") (pintype "passive"))
      (node (ref "R33") (pin "1") (pinfunction "1_1") (pintype "passive"))
    )
    (net (code "58") (name "Net-(T2-G)") (class "Default")
      (node (ref "R31") (pin "2") (pinfunction "2_2") (pintype "passive"))
      (node (ref "T2") (pin "3") (pinfunction "G_3") (pintype "passive"))
    )
    (net (code "59") (name "Net-(T3-B)") (class "Default")
      (node (ref "R15") (pin "1") (pinfunction "1_1") (pintype "passive"))
      (node (ref "R16") (pin "1") (pinfunction "1_1") (pintype "passive"))
      (node (ref "T3") (pin "1") (pinfunction "B_1") (pintype "passive"))
    )
    (net (code "60") (name "Net-(T3-C)") (class "Default")
      (node (ref "C30") (pin "2") (pinfunction "2_2") (pintype "passive"))
      (node (ref "R14") (pin "2") (pinfunction "2_2") (pintype "passive"))
      (node (ref "R17") (pin "1") (pinfunction "1_1") (pintype "passive"))
      (node (ref "T3") (pin "3") (pinfunction "C_3") (pintype "passive"))
    )
    (net (code "61") (name "Net-(U$1-1STLOBASE)") (class "Default")
      (node (ref "C5") (pin "1") (pinfunction "1_1") (pintype "passive"))
      (node (ref "U$1") (pin "1") (pinfunction "1STLOBASE_1") (pintype "bidirectional"))
    )
    (net (code "62") (name "Net-(U$1-1STLOOUT)") (class "Default")
      (node (ref "C34") (pin "2") (pinfunction "2_2") (pintype "passive"))
      (node (ref "U$1") (pin "3") (pinfunction "1STLOOUT_3") (pintype "bidirectional"))
    )
    (net (code "63") (name "Net-(U$1-1STMIXERIN1)") (class "Default")
      (node (ref "C15") (pin "1") (pinfunction "1_1") (pintype "passive"))
      (node (ref "U$1") (pin "22") (pinfunction "1STMIXERIN1_22") (pintype "bidirectional"))
    )
    (net (code "64") (name "Net-(U$1-1STMIXERIN2)") (class "Default")
      (node (ref "C21") (pin "2") (pinfunction "2_2") (pintype "passive"))
      (node (ref "U$1") (pin "21") (pinfunction "1STMIXERIN2_21") (pintype "bidirectional"))
    )
    (net (code "65") (name "Net-(U$1-1STMIXEROUT)") (class "Default")
      (node (ref "R4") (pin "1") (pinfunction "1_1") (pintype "passive"))
      (node (ref "U$1") (pin "20") (pinfunction "1STMIXEROUT_20") (pintype "bidirectional"))
    )
    (net (code "66") (name "Net-(U$1-2NDLOBASE)") (class "Default")
      (node (ref "C12") (pin "2") (pinfunction "2_2") (pintype "passive"))
      (node (ref "Q1") (pin "2") (pinfunction "2_2") (pintype "passive"))
      (node (ref "U$1") (pin "6") (pinfunction "2NDLOBASE_6") (pintype "bidirectional"))
    )
    (net (code "67") (name "Net-(U$1-2NDLOEMITTER)") (class "Default")
      (node (ref "C12") (pin "1") (pinfunction "1_1") (pintype "passive"))
      (node (ref "C13") (pin "2") (pinfunction "2_2") (pintype "passive"))
      (node (ref "U$1") (pin "5") (pinfunction "2NDLOEMITTER_5") (pintype "bidirectional"))
    )
    (net (code "68") (name "Net-(U$1-2NDMIXERIN)") (class "Default")
      (node (ref "R6") (pin "1") (pinfunction "1_1") (pintype "passive"))
      (node (ref "U$1") (pin "18") (pinfunction "2NDMIXERIN_18") (pintype "bidirectional"))
      (node (ref "U$3") (pin "P$1") (pinfunction "1_P$1") (pintype "bidirectional"))
    )
    (net (code "69") (name "Net-(U$1-2NDMIXEROUT)") (class "Default")
      (node (ref "U$1") (pin "7") (pinfunction "2NDMIXEROUT_7") (pintype "bidirectional"))
      (node (ref "U$2") (pin "P$1") (pinfunction "1_P$1") (pintype "bidirectional"))
    )
    (net (code "70") (name "Net-(U$1-DECOUPLE1)") (class "Default")
      (node (ref "C7") (pin "2") (pinfunction "2_2") (pintype "passive"))
      (node (ref "C8") (pin "1") (pinfunction "1_1") (pintype "passive"))
      (node (ref "U$1") (pin "10") (pinfunction "DECOUPLE1_10") (pintype "bidirectional"))
    )
    (net (code "71") (name "Net-(U$1-DECOUPLE2)") (class "Default")
      (node (ref "C7") (pin "1") (pinfunction "1_1") (pintype "passive"))
      (node (ref "U$1") (pin "11") (pinfunction "DECOUPLE2_11") (pintype "bidirectional"))
    )
    (net (code "72") (name "Net-(U$1-LIMITERIN)") (class "Default")
      (node (ref "U$1") (pin "9") (pinfunction "LIMITERIN_9") (pintype "bidirectional"))
      (node (ref "U$2") (pin "P$3") (pinfunction "3_P$3") (pintype "bidirectional"))
    )
    (net (code "73") (name "Net-(U$1-OPAMPIN+)") (class "Default")
      (node (ref "C6") (pin "2") (pinfunction "2_2") (pintype "passive"))
      (node (ref "U$1") (pin "12") (pinfunction "RSSI_12") (pintype "bidirectional"))
      (node (ref "U$1") (pin "14") (pinfunction "OPAMPIN+_14") (pintype "bidirectional"))
    )
    (net (code "74") (name "Net-(U$1-OPAMPIN-)") (class "Default")
      (node (ref "R7") (pin "1") (pinfunction "1_1") (pintype "passive"))
      (node (ref "U$1") (pin "15") (pinfunction "OPAMPIN-_15") (pintype "bidirectional"))
      (node (ref "U$1") (pin "16") (pinfunction "OPAMPOUT_16") (pintype "bidirectional"))
    )
    (net (code "75") (name "Net-(U$3-3)") (class "Default")
      (node (ref "R4") (pin "2") (pinfunction "2_2") (pintype "passive"))
      (node (ref "U$3") (pin "P$3") (pinfunction "3_P$3") (pintype "bidirectional"))
    )
    (net (code "76") (name "Net-(U$4-FMIN)") (class "Default")
      (node (ref "R18") (pin "1") (pinfunction "1_1") (pintype "passive"))
      (node (ref "U$4") (pin "11") (pinfunction "FMIN_11") (pintype "bidirectional"))
    )
    (net (code "77") (name "Net-(U$4-PD1)") (class "Default")
      (node (ref "R16") (pin "2") (pinfunction "2_2") (pintype "passive"))
      (node (ref "U$4") (pin "14") (pinfunction "PD1_14") (pintype "bidirectional"))
    )
    (net (code "78") (name "Net-(U$4-XIN)") (class "Default")
      (node (ref "C32") (pin "1") (pinfunction "1_1") (pintype "passive"))
      (node (ref "Q2") (pin "1") (pinfunction "1_1") (pintype "passive"))
      (node (ref "U$4") (pin "2") (pinfunction "XIN_2") (pintype "bidirectional"))
    )
    (net (code "79") (name "VCC") (class "Default")
      (node (ref "C10") (pin "2") (pinfunction "2_2") (pintype "passive"))
      (node (ref "C11") (pin "2") (pinfunction "2_2") (pintype "passive"))
      (node (ref "C13") (pin "1") (pinfunction "1_1") (pintype "passive"))
      (node (ref "C14") (pin "2") (pinfunction "2_2") (pintype "passive"))
      (node (ref "C26") (pin "2") (pinfunction "2_2") (pintype "passive"))
      (node (ref "C39") (pin "1") (pinfunction "1_1") (pintype "passive"))
      (node (ref "C41") (pin "1") (pinfunction "1_1") (pintype "passive"))
      (node (ref "C43") (pin "+") (pinfunction "+_+") (pintype "passive"))
      (node (ref "C9") (pin "1") (pinfunction "1_1") (pintype "passive"))
      (node (ref "IC1") (pin "6") (pinfunction "VS_6") (pintype "power_in"))
      (node (ref "L2") (pin "2") (pinfunction "A_2") (pintype "passive"))
      (node (ref "Q1") (pin "1") (pinfunction "1_1") (pintype "passive"))
      (node (ref "R17") (pin "2") (pinfunction "2_2") (pintype "passive"))
      (node (ref "R2") (pin "2") (pinfunction "2_2") (pintype "passive"))
      (node (ref "R23") (pin "1") (pinfunction "1_1") (pintype "passive"))
      (node (ref "R28") (pin "2") (pinfunction "2_2") (pintype "passive"))
      (node (ref "R5") (pin "2") (pinfunction "2_2") (pintype "passive"))
      (node (ref "R6") (pin "2") (pinfunction "2_2") (pintype "passive"))
      (node (ref "T1") (pin "C") (pinfunction "C_C") (pintype "passive"))
      (node (ref "U$1") (pin "19") (pinfunction "VCC2_19") (pintype "bidirectional"))
      (node (ref "U$1") (pin "4") (pinfunction "VCC1_4") (pintype "bidirectional"))
      (node (ref "U$3") (pin "P$2") (pinfunction "2_P$2") (pintype "bidirectional"))
      (node (ref "U$4") (pin "12") (pinfunction "VDD1_12") (pintype "bidirectional"))
      (node (ref "U$4") (pin "13") (pinfunction "VDD2_13") (pintype "bidirectional"))
    )
    (net (code "80") (name "unconnected-(IC1-GAIN-Pad1)") (class "Default")
      (node (ref "IC1") (pin "1") (pinfunction "GAIN_1") (pintype "passive"))
    )
    (net (code "81") (name "unconnected-(IC1-GAIN-Pad8)") (class "Default")
      (node (ref "IC1") (pin "8") (pinfunction "GAIN_8") (pintype "passive"))
    )
    (net (code "82") (name "unconnected-(IC2-ADC6-Pad19)") (class "Default")
      (node (ref "IC2") (pin "19") (pinfunction "ADC6_19") (pintype "bidirectional"))
    )
    (net (code "83") (name "unconnected-(U$1-1STLOEMITTER-Pad2)") (class "Default")
      (node (ref "U$1") (pin "2") (pinfunction "1STLOEMITTER_2") (pintype "bidirectional"))
    )
    (net (code "84") (name "unconnected-(U$1-VARICAPA-Pad23)") (class "Default")
      (node (ref "U$1") (pin "23") (pinfunction "VARICAPA_23") (pintype "bidirectional"))
    )
    (net (code "85") (name "unconnected-(U$1-VARICAPC-Pad24)") (class "Default")
      (node (ref "U$1") (pin "24") (pinfunction "VARICAPC_24") (pintype "bidirectional"))
    )
    (net (code "86") (name "unconnected-(U$4-AMIN-Pad10)") (class "Default")
      (node (ref "U$4") (pin "10") (pinfunction "AMIN_10") (pintype "bidirectional"))
    )
    (net (code "87") (name "unconnected-(U$4-BO1-Pad7)") (class "Default")
      (node (ref "U$4") (pin "7") (pinfunction "BO1_7") (pintype "bidirectional"))
    )
    (net (code "88") (name "unconnected-(U$4-BO2-Pad8)") (class "Default")
      (node (ref "U$4") (pin "8") (pinfunction "BO2_8") (pintype "bidirectional"))
    )
    (net (code "89") (name "unconnected-(U$4-BO3-Pad9)") (class "Default")
      (node (ref "U$4") (pin "9") (pinfunction "BO3_9") (pintype "bidirectional"))
    )
    (net (code "90") (name "unconnected-(U$4-PD2-Pad15)") (class "Default")
      (node (ref "U$4") (pin "15") (pinfunction "PD2_15") (pintype "bidirectional"))
    )
    (net (code "91") (name "unconnected-(U$4-SYC-Pad6)") (class "Default")
      (node (ref "U$4") (pin "6") (pinfunction "SYC_6") (pintype "bidirectional"))
    )
    (net (code "92") (name "unconnected-(X2-2-Pad2@2)") (class "Default")
      (node (ref "X2") (pin "2@2") (pinfunction "2_2@2") (pintype "passive"))
    )
    (net (code "93") (name "unconnected-(X5B-S-Pad2)") (class "Default")
      (node (ref "X5") (pin "2") (pinfunction "S_2") (pintype "passive"))
    )
  )
)
